# MainMatrix.net
KiCad netlist of a schematic drawn in EAGLE
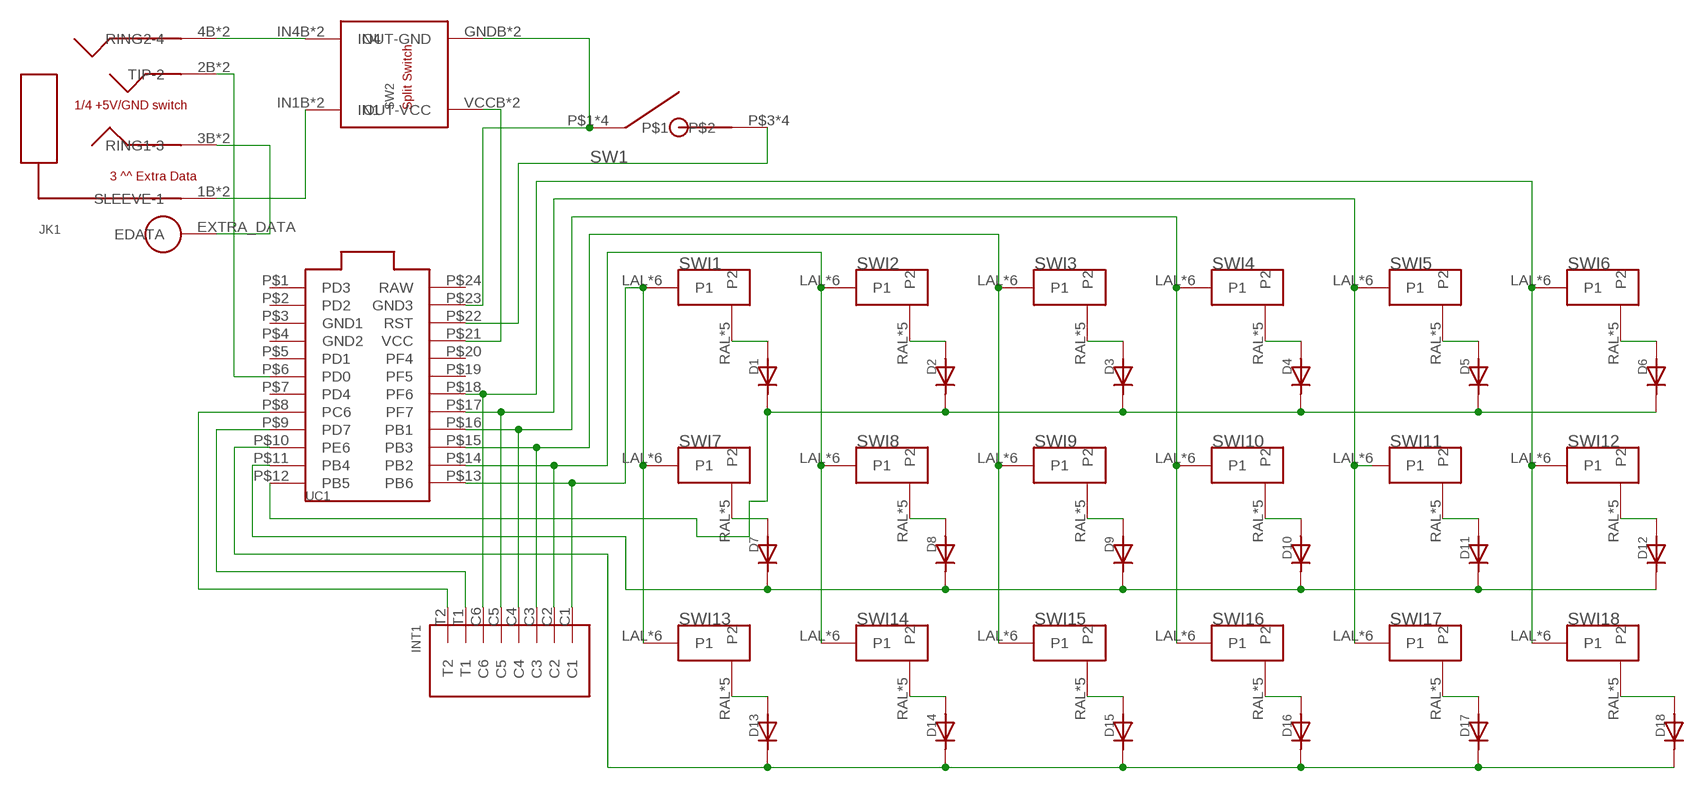
[diagram p0: schematic, sheet 1]

(export (version "E")
  (design (tool "Eeschema 10.0.6"))
  (components
    (comp (ref "D1")
      (value "DIODE")
      (footprint "eagle-import:DIODE_COMBO")
      (libsource (lib "eagle-import") (part "DIODE"))
    )
    (comp (ref "D2")
      (value "DIODE")
      (footprint "eagle-import:DIODE_COMBO")
      (libsource (lib "eagle-import") (part "DIODE"))
    )
    (comp (ref "D3")
      (value "DIODE")
      (footprint "eagle-import:DIODE_COMBO")
      (libsource (lib "eagle-import") (part "DIODE"))
    )
    (comp (ref "D4")
      (value "DIODE")
      (footprint "eagle-import:DIODE_COMBO")
      (libsource (lib "eagle-import") (part "DIODE"))
    )
    (comp (ref "D5")
      (value "DIODE")
      (footprint "eagle-import:DIODE_COMBO")
      (libsource (lib "eagle-import") (part "DIODE"))
    )
    (comp (ref "D6")
      (value "DIODE")
      (footprint "eagle-import:DIODE_COMBO")
      (libsource (lib "eagle-import") (part "DIODE"))
    )
    (comp (ref "D7")
      (value "DIODE")
      (footprint "eagle-import:DIODE_COMBO")
      (libsource (lib "eagle-import") (part "DIODE"))
    )
    (comp (ref "D8")
      (value "DIODE")
      (footprint "eagle-import:DIODE_COMBO")
      (libsource (lib "eagle-import") (part "DIODE"))
    )
    (comp (ref "D9")
      (value "DIODE")
      (footprint "eagle-import:DIODE_COMBO")
      (libsource (lib "eagle-import") (part "DIODE"))
    )
    (comp (ref "D10")
      (value "DIODE")
      (footprint "eagle-import:DIODE_COMBO")
      (libsource (lib "eagle-import") (part "DIODE"))
    )
    (comp (ref "D11")
      (value "DIODE")
      (footprint "eagle-import:DIODE_COMBO")
      (libsource (lib "eagle-import") (part "DIODE"))
    )
    (comp (ref "D12")
      (value "DIODE")
      (footprint "eagle-import:DIODE_COMBO")
      (libsource (lib "eagle-import") (part "DIODE"))
    )
    (comp (ref "D13")
      (value "DIODE")
      (footprint "eagle-import:DIODE_COMBO")
      (libsource (lib "eagle-import") (part "DIODE"))
    )
    (comp (ref "D14")
      (value "DIODE")
      (footprint "eagle-import:DIODE_COMBO")
      (libsource (lib "eagle-import") (part "DIODE"))
    )
    (comp (ref "D15")
      (value "DIODE")
      (footprint "eagle-import:DIODE_COMBO")
      (libsource (lib "eagle-import") (part "DIODE"))
    )
    (comp (ref "D16")
      (value "DIODE")
      (footprint "eagle-import:DIODE_COMBO")
      (libsource (lib "eagle-import") (part "DIODE"))
    )
    (comp (ref "D17")
      (value "DIODE")
      (footprint "eagle-import:DIODE_COMBO")
      (libsource (lib "eagle-import") (part "DIODE"))
    )
    (comp (ref "D18")
      (value "DIODE")
      (footprint "eagle-import:DIODE_COMBO")
      (libsource (lib "eagle-import") (part "DIODE"))
    )
    (comp (ref "INT1")
      (value "INTRCNNT4X2")
      (footprint "eagle-import:INTRRIBBON")
      (libsource (lib "eagle-import") (part "INTRCNNT4X2"))
    )
    (comp (ref "JK1")
      (value "TRRSJACKUNDER")
      (footprint "eagle-import:TRRSJACK")
      (libsource (lib "eagle-import") (part "TRRSJACKUNDER"))
    )
    (comp (ref "SW1")
      (value "RSTSWSMD")
      (footprint "eagle-import:FLATSWT")
      (libsource (lib "eagle-import") (part "RSTSWSMD"))
    )
    (comp (ref "SW2")
      (value "TRANSFERPADDY")
      (footprint "eagle-import:TRANSFER_PADS")
      (libsource (lib "eagle-import") (part "TRANSFERPADDY"))
    )
    (comp (ref "SWI1")
      (value "MX/ALPSDOUBLESIDED")
      (footprint "eagle-import:DOUBLED_MX_ALPS")
      (libsource (lib "eagle-import") (part "MX/ALPSDOUBLESIDED"))
    )
    (comp (ref "SWI2")
      (value "MX/ALPSDOUBLESIDED")
      (footprint "eagle-import:DOUBLED_MX_ALPS")
      (libsource (lib "eagle-import") (part "MX/ALPSDOUBLESIDED"))
    )
    (comp (ref "SWI3")
      (value "MX/ALPSDOUBLESIDED")
      (footprint "eagle-import:DOUBLED_MX_ALPS")
      (libsource (lib "eagle-import") (part "MX/ALPSDOUBLESIDED"))
    )
    (comp (ref "SWI4")
      (value "MX/ALPSDOUBLESIDED")
      (footprint "eagle-import:DOUBLED_MX_ALPS")
      (libsource (lib "eagle-import") (part "MX/ALPSDOUBLESIDED"))
    )
    (comp (ref "SWI5")
      (value "MX/ALPSDOUBLESIDED")
      (footprint "eagle-import:DOUBLED_MX_ALPS")
      (libsource (lib "eagle-import") (part "MX/ALPSDOUBLESIDED"))
    )
    (comp (ref "SWI6")
      (value "MX/ALPSDOUBLESIDED")
      (footprint "eagle-import:DOUBLED_MX_ALPS")
      (libsource (lib "eagle-import") (part "MX/ALPSDOUBLESIDED"))
    )
    (comp (ref "SWI7")
      (value "MX/ALPSDOUBLESIDED")
      (footprint "eagle-import:DOUBLED_MX_ALPS")
      (libsource (lib "eagle-import") (part "MX/ALPSDOUBLESIDED"))
    )
    (comp (ref "SWI8")
      (value "MX/ALPSDOUBLESIDED")
      (footprint "eagle-import:DOUBLED_MX_ALPS")
      (libsource (lib "eagle-import") (part "MX/ALPSDOUBLESIDED"))
    )
    (comp (ref "SWI9")
      (value "MX/ALPSDOUBLESIDED")
      (footprint "eagle-import:DOUBLED_MX_ALPS")
      (libsource (lib "eagle-import") (part "MX/ALPSDOUBLESIDED"))
    )
    (comp (ref "SWI10")
      (value "MX/ALPSDOUBLESIDED")
      (footprint "eagle-import:DOUBLED_MX_ALPS")
      (libsource (lib "eagle-import") (part "MX/ALPSDOUBLESIDED"))
    )
    (comp (ref "SWI11")
      (value "MX/ALPSDOUBLESIDED")
      (footprint "eagle-import:DOUBLED_MX_ALPS")
      (libsource (lib "eagle-import") (part "MX/ALPSDOUBLESIDED"))
    )
    (comp (ref "SWI12")
      (value "MX/ALPSDOUBLESIDED")
      (footprint "eagle-import:DOUBLED_MX_ALPS")
      (libsource (lib "eagle-import") (part "MX/ALPSDOUBLESIDED"))
    )
    (comp (ref "SWI13")
      (value "MX/ALPSDOUBLESIDED")
      (footprint "eagle-import:DOUBLED_MX_ALPS")
      (libsource (lib "eagle-import") (part "MX/ALPSDOUBLESIDED"))
    )
    (comp (ref "SWI14")
      (value "MX/ALPSDOUBLESIDED")
      (footprint "eagle-import:DOUBLED_MX_ALPS")
      (libsource (lib "eagle-import") (part "MX/ALPSDOUBLESIDED"))
    )
    (comp (ref "SWI15")
      (value "MX/ALPSDOUBLESIDED")
      (footprint "eagle-import:DOUBLED_MX_ALPS")
      (libsource (lib "eagle-import") (part "MX/ALPSDOUBLESIDED"))
    )
    (comp (ref "SWI16")
      (value "MX/ALPSDOUBLESIDED")
      (footprint "eagle-import:DOUBLED_MX_ALPS")
      (libsource (lib "eagle-import") (part "MX/ALPSDOUBLESIDED"))
    )
    (comp (ref "SWI17")
      (value "MX/ALPSDOUBLESIDED")
      (footprint "eagle-import:DOUBLED_MX_ALPS")
      (libsource (lib "eagle-import") (part "MX/ALPSDOUBLESIDED"))
    )
    (comp (ref "SWI18")
      (value "MX/ALPSDOUBLESIDED")
      (footprint "eagle-import:DOUBLED_MX_ALPS")
      (libsource (lib "eagle-import") (part "MX/ALPSDOUBLESIDED"))
    )
    (comp (ref "UC1")
      (value "PROMICROUNDER")
      (footprint "eagle-import:PROMICRO_UNDER")
      (libsource (lib "eagle-import") (part "PROMICROUNDER"))
    )
  )
  (nets
    (net (code "1") (name "Net-(D1-AN-PadANOSB)") (class "Default")
      (node (ref "D1") (pin "ANOSB") (pinfunction "AN_ANOSB") (pintype "bidirectional"))
      (node (ref "D1") (pin "ANOST") (pinfunction "AN_ANOST") (pintype "bidirectional"))
      (node (ref "D1") (pin "ANOT") (pinfunction "AN_ANOT") (pintype "bidirectional"))
      (node (ref "SWI1") (pin "RAL") (pinfunction "P2_RAL") (pintype "bidirectional"))
      (node (ref "SWI1") (pin "RAR") (pinfunction "P2_RAR") (pintype "bidirectional"))
      (node (ref "SWI1") (pin "RCL") (pinfunction "P2_RCL") (pintype "bidirectional"))
      (node (ref "SWI1") (pin "RCR") (pinfunction "P2_RCR") (pintype "bidirectional"))
      (node (ref "SWI1") (pin "RLMID") (pinfunction "P2_RLMID") (pintype "bidirectional"))
    )
    (net (code "2") (name "Net-(D2-AN-PadANOSB)") (class "Default")
      (node (ref "D2") (pin "ANOSB") (pinfunction "AN_ANOSB") (pintype "bidirectional"))
      (node (ref "D2") (pin "ANOST") (pinfunction "AN_ANOST") (pintype "bidirectional"))
      (node (ref "D2") (pin "ANOT") (pinfunction "AN_ANOT") (pintype "bidirectional"))
      (node (ref "SWI2") (pin "RAL") (pinfunction "P2_RAL") (pintype "bidirectional"))
      (node (ref "SWI2") (pin "RAR") (pinfunction "P2_RAR") (pintype "bidirectional"))
      (node (ref "SWI2") (pin "RCL") (pinfunction "P2_RCL") (pintype "bidirectional"))
      (node (ref "SWI2") (pin "RCR") (pinfunction "P2_RCR") (pintype "bidirectional"))
      (node (ref "SWI2") (pin "RLMID") (pinfunction "P2_RLMID") (pintype "bidirectional"))
    )
    (net (code "3") (name "Net-(D3-AN-PadANOSB)") (class "Default")
      (node (ref "D3") (pin "ANOSB") (pinfunction "AN_ANOSB") (pintype "bidirectional"))
      (node (ref "D3") (pin "ANOST") (pinfunction "AN_ANOST") (pintype "bidirectional"))
      (node (ref "D3") (pin "ANOT") (pinfunction "AN_ANOT") (pintype "bidirectional"))
      (node (ref "SWI3") (pin "RAL") (pinfunction "P2_RAL") (pintype "bidirectional"))
      (node (ref "SWI3") (pin "RAR") (pinfunction "P2_RAR") (pintype "bidirectional"))
      (node (ref "SWI3") (pin "RCL") (pinfunction "P2_RCL") (pintype "bidirectional"))
      (node (ref "SWI3") (pin "RCR") (pinfunction "P2_RCR") (pintype "bidirectional"))
      (node (ref "SWI3") (pin "RLMID") (pinfunction "P2_RLMID") (pintype "bidirectional"))
    )
    (net (code "4") (name "Net-(D4-AN-PadANOSB)") (class "Default")
      (node (ref "D4") (pin "ANOSB") (pinfunction "AN_ANOSB") (pintype "bidirectional"))
      (node (ref "D4") (pin "ANOST") (pinfunction "AN_ANOST") (pintype "bidirectional"))
      (node (ref "D4") (pin "ANOT") (pinfunction "AN_ANOT") (pintype "bidirectional"))
      (node (ref "SWI4") (pin "RAL") (pinfunction "P2_RAL") (pintype "bidirectional"))
      (node (ref "SWI4") (pin "RAR") (pinfunction "P2_RAR") (pintype "bidirectional"))
      (node (ref "SWI4") (pin "RCL") (pinfunction "P2_RCL") (pintype "bidirectional"))
      (node (ref "SWI4") (pin "RCR") (pinfunction "P2_RCR") (pintype "bidirectional"))
      (node (ref "SWI4") (pin "RLMID") (pinfunction "P2_RLMID") (pintype "bidirectional"))
    )
    (net (code "5") (name "Net-(D5-AN-PadANOSB)") (class "Default")
      (node (ref "D5") (pin "ANOSB") (pinfunction "AN_ANOSB") (pintype "bidirectional"))
      (node (ref "D5") (pin "ANOST") (pinfunction "AN_ANOST") (pintype "bidirectional"))
      (node (ref "D5") (pin "ANOT") (pinfunction "AN_ANOT") (pintype "bidirectional"))
      (node (ref "SWI5") (pin "RAL") (pinfunction "P2_RAL") (pintype "bidirectional"))
      (node (ref "SWI5") (pin "RAR") (pinfunction "P2_RAR") (pintype "bidirectional"))
      (node (ref "SWI5") (pin "RCL") (pinfunction "P2_RCL") (pintype "bidirectional"))
      (node (ref "SWI5") (pin "RCR") (pinfunction "P2_RCR") (pintype "bidirectional"))
      (node (ref "SWI5") (pin "RLMID") (pinfunction "P2_RLMID") (pintype "bidirectional"))
    )
    (net (code "6") (name "Net-(D6-AN-PadANOSB)") (class "Default")
      (node (ref "D6") (pin "ANOSB") (pinfunction "AN_ANOSB") (pintype "bidirectional"))
      (node (ref "D6") (pin "ANOST") (pinfunction "AN_ANOST") (pintype "bidirectional"))
      (node (ref "D6") (pin "ANOT") (pinfunction "AN_ANOT") (pintype "bidirectional"))
      (node (ref "SWI6") (pin "RAL") (pinfunction "P2_RAL") (pintype "bidirectional"))
      (node (ref "SWI6") (pin "RAR") (pinfunction "P2_RAR") (pintype "bidirectional"))
      (node (ref "SWI6") (pin "RCL") (pinfunction "P2_RCL") (pintype "bidirectional"))
      (node (ref "SWI6") (pin "RCR") (pinfunction "P2_RCR") (pintype "bidirectional"))
      (node (ref "SWI6") (pin "RLMID") (pinfunction "P2_RLMID") (pintype "bidirectional"))
    )
    (net (code "7") (name "Net-(D7-AN-PadANOSB)") (class "Default")
      (node (ref "D7") (pin "ANOSB") (pinfunction "AN_ANOSB") (pintype "bidirectional"))
      (node (ref "D7") (pin "ANOST") (pinfunction "AN_ANOST") (pintype "bidirectional"))
      (node (ref "D7") (pin "ANOT") (pinfunction "AN_ANOT") (pintype "bidirectional"))
      (node (ref "SWI7") (pin "RAL") (pinfunction "P2_RAL") (pintype "bidirectional"))
      (node (ref "SWI7") (pin "RAR") (pinfunction "P2_RAR") (pintype "bidirectional"))
      (node (ref "SWI7") (pin "RCL") (pinfunction "P2_RCL") (pintype "bidirectional"))
      (node (ref "SWI7") (pin "RCR") (pinfunction "P2_RCR") (pintype "bidirectional"))
      (node (ref "SWI7") (pin "RLMID") (pinfunction "P2_RLMID") (pintype "bidirectional"))
    )
    (net (code "8") (name "Net-(D8-AN-PadANOSB)") (class "Default")
      (node (ref "D8") (pin "ANOSB") (pinfunction "AN_ANOSB") (pintype "bidirectional"))
      (node (ref "D8") (pin "ANOST") (pinfunction "AN_ANOST") (pintype "bidirectional"))
      (node (ref "D8") (pin "ANOT") (pinfunction "AN_ANOT") (pintype "bidirectional"))
      (node (ref "SWI8") (pin "RAL") (pinfunction "P2_RAL") (pintype "bidirectional"))
      (node (ref "SWI8") (pin "RAR") (pinfunction "P2_RAR") (pintype "bidirectional"))
      (node (ref "SWI8") (pin "RCL") (pinfunction "P2_RCL") (pintype "bidirectional"))
      (node (ref "SWI8") (pin "RCR") (pinfunction "P2_RCR") (pintype "bidirectional"))
      (node (ref "SWI8") (pin "RLMID") (pinfunction "P2_RLMID") (pintype "bidirectional"))
    )
    (net (code "9") (name "Net-(D9-AN-PadANOSB)") (class "Default")
      (node (ref "D9") (pin "ANOSB") (pinfunction "AN_ANOSB") (pintype "bidirectional"))
      (node (ref "D9") (pin "ANOST") (pinfunction "AN_ANOST") (pintype "bidirectional"))
      (node (ref "D9") (pin "ANOT") (pinfunction "AN_ANOT") (pintype "bidirectional"))
      (node (ref "SWI9") (pin "RAL") (pinfunction "P2_RAL") (pintype "bidirectional"))
      (node (ref "SWI9") (pin "RAR") (pinfunction "P2_RAR") (pintype "bidirectional"))
      (node (ref "SWI9") (pin "RCL") (pinfunction "P2_RCL") (pintype "bidirectional"))
      (node (ref "SWI9") (pin "RCR") (pinfunction "P2_RCR") (pintype "bidirectional"))
      (node (ref "SWI9") (pin "RLMID") (pinfunction "P2_RLMID") (pintype "bidirectional"))
    )
    (net (code "10") (name "Net-(D10-AN-PadANOSB)") (class "Default")
      (node (ref "D10") (pin "ANOSB") (pinfunction "AN_ANOSB") (pintype "bidirectional"))
      (node (ref "D10") (pin "ANOST") (pinfunction "AN_ANOST") (pintype "bidirectional"))
      (node (ref "D10") (pin "ANOT") (pinfunction "AN_ANOT") (pintype "bidirectional"))
      (node (ref "SWI10") (pin "RAL") (pinfunction "P2_RAL") (pintype "bidirectional"))
      (node (ref "SWI10") (pin "RAR") (pinfunction "P2_RAR") (pintype "bidirectional"))
      (node (ref "SWI10") (pin "RCL") (pinfunction "P2_RCL") (pintype "bidirectional"))
      (node (ref "SWI10") (pin "RCR") (pinfunction "P2_RCR") (pintype "bidirectional"))
      (node (ref "SWI10") (pin "RLMID") (pinfunction "P2_RLMID") (pintype "bidirectional"))
    )
    (net (code "11") (name "Net-(D11-AN-PadANOSB)") (class "Default")
      (node (ref "D11") (pin "ANOSB") (pinfunction "AN_ANOSB") (pintype "bidirectional"))
      (node (ref "D11") (pin "ANOST") (pinfunction "AN_ANOST") (pintype "bidirectional"))
      (node (ref "D11") (pin "ANOT") (pinfunction "AN_ANOT") (pintype "bidirectional"))
      (node (ref "SWI11") (pin "RAL") (pinfunction "P2_RAL") (pintype "bidirectional"))
      (node (ref "SWI11") (pin "RAR") (pinfunction "P2_RAR") (pintype "bidirectional"))
      (node (ref "SWI11") (pin "RCL") (pinfunction "P2_RCL") (pintype "bidirectional"))
      (node (ref "SWI11") (pin "RCR") (pinfunction "P2_RCR") (pintype "bidirectional"))
      (node (ref "SWI11") (pin "RLMID") (pinfunction "P2_RLMID") (pintype "bidirectional"))
    )
    (net (code "12") (name "Net-(D12-AN-PadANOSB)") (class "Default")
      (node (ref "D12") (pin "ANOSB") (pinfunction "AN_ANOSB") (pintype "bidirectional"))
      (node (ref "D12") (pin "ANOST") (pinfunction "AN_ANOST") (pintype "bidirectional"))
      (node (ref "D12") (pin "ANOT") (pinfunction "AN_ANOT") (pintype "bidirectional"))
      (node (ref "SWI12") (pin "RAL") (pinfunction "P2_RAL") (pintype "bidirectional"))
      (node (ref "SWI12") (pin "RAR") (pinfunction "P2_RAR") (pintype "bidirectional"))
      (node (ref "SWI12") (pin "RCL") (pinfunction "P2_RCL") (pintype "bidirectional"))
      (node (ref "SWI12") (pin "RCR") (pinfunction "P2_RCR") (pintype "bidirectional"))
      (node (ref "SWI12") (pin "RLMID") (pinfunction "P2_RLMID") (pintype "bidirectional"))
    )
    (net (code "13") (name "Net-(D13-AN-PadANOSB)") (class "Default")
      (node (ref "D13") (pin "ANOSB") (pinfunction "AN_ANOSB") (pintype "bidirectional"))
      (node (ref "D13") (pin "ANOST") (pinfunction "AN_ANOST") (pintype "bidirectional"))
      (node (ref "D13") (pin "ANOT") (pinfunction "AN_ANOT") (pintype "bidirectional"))
      (node (ref "SWI13") (pin "RAL") (pinfunction "P2_RAL") (pintype "bidirectional"))
      (node (ref "SWI13") (pin "RAR") (pinfunction "P2_RAR") (pintype "bidirectional"))
      (node (ref "SWI13") (pin "RCL") (pinfunction "P2_RCL") (pintype "bidirectional"))
      (node (ref "SWI13") (pin "RCR") (pinfunction "P2_RCR") (pintype "bidirectional"))
      (node (ref "SWI13") (pin "RLMID") (pinfunction "P2_RLMID") (pintype "bidirectional"))
    )
    (net (code "14") (name "Net-(D14-AN-PadANOSB)") (class "Default")
      (node (ref "D14") (pin "ANOSB") (pinfunction "AN_ANOSB") (pintype "bidirectional"))
      (node (ref "D14") (pin "ANOST") (pinfunction "AN_ANOST") (pintype "bidirectional"))
      (node (ref "D14") (pin "ANOT") (pinfunction "AN_ANOT") (pintype "bidirectional"))
      (node (ref "SWI14") (pin "RAL") (pinfunction "P2_RAL") (pintype "bidirectional"))
      (node (ref "SWI14") (pin "RAR") (pinfunction "P2_RAR") (pintype "bidirectional"))
      (node (ref "SWI14") (pin "RCL") (pinfunction "P2_RCL") (pintype "bidirectional"))
      (node (ref "SWI14") (pin "RCR") (pinfunction "P2_RCR") (pintype "bidirectional"))
      (node (ref "SWI14") (pin "RLMID") (pinfunction "P2_RLMID") (pintype "bidirectional"))
    )
    (net (code "15") (name "Net-(D15-AN-PadANOSB)") (class "Default")
      (node (ref "D15") (pin "ANOSB") (pinfunction "AN_ANOSB") (pintype "bidirectional"))
      (node (ref "D15") (pin "ANOST") (pinfunction "AN_ANOST") (pintype "bidirectional"))
      (node (ref "D15") (pin "ANOT") (pinfunction "AN_ANOT") (pintype "bidirectional"))
      (node (ref "SWI15") (pin "RAL") (pinfunction "P2_RAL") (pintype "bidirectional"))
      (node (ref "SWI15") (pin "RAR") (pinfunction "P2_RAR") (pintype "bidirectional"))
      (node (ref "SWI15") (pin "RCL") (pinfunction "P2_RCL") (pintype "bidirectional"))
      (node (ref "SWI15") (pin "RCR") (pinfunction "P2_RCR") (pintype "bidirectional"))
      (node (ref "SWI15") (pin "RLMID") (pinfunction "P2_RLMID") (pintype "bidirectional"))
    )
    (net (code "16") (name "Net-(D16-AN-PadANOSB)") (class "Default")
      (node (ref "D16") (pin "ANOSB") (pinfunction "AN_ANOSB") (pintype "bidirectional"))
      (node (ref "D16") (pin "ANOST") (pinfunction "AN_ANOST") (pintype "bidirectional"))
      (node (ref "D16") (pin "ANOT") (pinfunction "AN_ANOT") (pintype "bidirectional"))
      (node (ref "SWI16") (pin "RAL") (pinfunction "P2_RAL") (pintype "bidirectional"))
      (node (ref "SWI16") (pin "RAR") (pinfunction "P2_RAR") (pintype "bidirectional"))
      (node (ref "SWI16") (pin "RCL") (pinfunction "P2_RCL") (pintype "bidirectional"))
      (node (ref "SWI16") (pin "RCR") (pinfunction "P2_RCR") (pintype "bidirectional"))
      (node (ref "SWI16") (pin "RLMID") (pinfunction "P2_RLMID") (pintype "bidirectional"))
    )
    (net (code "17") (name "Net-(D17-AN-PadANOSB)") (class "Default")
      (node (ref "D17") (pin "ANOSB") (pinfunction "AN_ANOSB") (pintype "bidirectional"))
      (node (ref "D17") (pin "ANOST") (pinfunction "AN_ANOST") (pintype "bidirectional"))
      (node (ref "D17") (pin "ANOT") (pinfunction "AN_ANOT") (pintype "bidirectional"))
      (node (ref "SWI17") (pin "RAL") (pinfunction "P2_RAL") (pintype "bidirectional"))
      (node (ref "SWI17") (pin "RAR") (pinfunction "P2_RAR") (pintype "bidirectional"))
      (node (ref "SWI17") (pin "RCL") (pinfunction "P2_RCL") (pintype "bidirectional"))
      (node (ref "SWI17") (pin "RCR") (pinfunction "P2_RCR") (pintype "bidirectional"))
      (node (ref "SWI17") (pin "RLMID") (pinfunction "P2_RLMID") (pintype "bidirectional"))
    )
    (net (code "18") (name "Net-(D18-AN-PadANOSB)") (class "Default")
      (node (ref "D18") (pin "ANOSB") (pinfunction "AN_ANOSB") (pintype "bidirectional"))
      (node (ref "D18") (pin "ANOST") (pinfunction "AN_ANOST") (pintype "bidirectional"))
      (node (ref "D18") (pin "ANOT") (pinfunction "AN_ANOT") (pintype "bidirectional"))
      (node (ref "SWI18") (pin "RAL") (pinfunction "P2_RAL") (pintype "bidirectional"))
      (node (ref "SWI18") (pin "RAR") (pinfunction "P2_RAR") (pintype "bidirectional"))
      (node (ref "SWI18") (pin "RCL") (pinfunction "P2_RCL") (pintype "bidirectional"))
      (node (ref "SWI18") (pin "RCR") (pinfunction "P2_RCR") (pintype "bidirectional"))
      (node (ref "SWI18") (pin "RLMID") (pinfunction "P2_RLMID") (pintype "bidirectional"))
    )
    (net (code "19") (name "Net-(JK1-EDATA)") (class "Default")
      (node (ref "JK1") (pin "3B") (pinfunction "RING1-3_3B") (pintype "bidirectional"))
      (node (ref "JK1") (pin "3T") (pinfunction "RING1-3_3T") (pintype "bidirectional"))
      (node (ref "JK1") (pin "EXTRA_DATA") (pinfunction "EDATA_EXTRA_DATA") (pintype "bidirectional"))
    )
    (net (code "20") (name "Net-(JK1-RING2-4-Pad4B)") (class "Default")
      (node (ref "JK1") (pin "4B") (pinfunction "RING2-4_4B") (pintype "bidirectional"))
      (node (ref "JK1") (pin "4T") (pinfunction "RING2-4_4T") (pintype "bidirectional"))
      (node (ref "SW2") (pin "IN4B") (pinfunction "IN4_IN4B") (pintype "bidirectional"))
      (node (ref "SW2") (pin "IN4T") (pinfunction "IN4_IN4T") (pintype "bidirectional"))
    )
    (net (code "21") (name "Net-(JK1-SLEEVE-1-Pad1B)") (class "Default")
      (node (ref "JK1") (pin "1B") (pinfunction "SLEEVE-1_1B") (pintype "bidirectional"))
      (node (ref "JK1") (pin "1T") (pinfunction "SLEEVE-1_1T") (pintype "bidirectional"))
      (node (ref "SW2") (pin "IN1B") (pinfunction "IN1_IN1B") (pintype "bidirectional"))
      (node (ref "SW2") (pin "IN1T") (pinfunction "IN1_IN1T") (pintype "bidirectional"))
    )
    (net (code "22") (name "Net-(UC1-GND3)") (class "Default")
      (node (ref "SW1") (pin "P$1") (pinfunction "P$1_P$1") (pintype "bidirectional"))
      (node (ref "SW1") (pin "P$2") (pinfunction "P$1_P$2") (pintype "bidirectional"))
      (node (ref "SW1") (pin "P$5") (pinfunction "P$1_P$5") (pintype "bidirectional"))
      (node (ref "SW1") (pin "P$6") (pinfunction "P$1_P$6") (pintype "bidirectional"))
      (node (ref "SW2") (pin "GNDB") (pinfunction "OUT-GND_GNDB") (pintype "bidirectional"))
      (node (ref "SW2") (pin "GNDT") (pinfunction "OUT-GND_GNDT") (pintype "bidirectional"))
      (node (ref "UC1") (pin "P$23") (pinfunction "GND3_P$23") (pintype "bidirectional"))
    )
    (net (code "23") (name "Net-(UC1-PB1)") (class "Default")
      (node (ref "INT1") (pin "C4") (pinfunction "C4_C4") (pintype "bidirectional"))
      (node (ref "SWI10") (pin "LAL") (pinfunction "P1_LAL") (pintype "bidirectional"))
      (node (ref "SWI10") (pin "LAR") (pinfunction "P1_LAR") (pintype "bidirectional"))
      (node (ref "SWI10") (pin "LCL") (pinfunction "P1_LCL") (pintype "bidirectional"))
      (node (ref "SWI10") (pin "LCR") (pinfunction "P1_LCR") (pintype "bidirectional"))
      (node (ref "SWI10") (pin "LLP") (pinfunction "P1_LLP") (pintype "bidirectional"))
      (node (ref "SWI10") (pin "LRLP") (pinfunction "P1_LRLP") (pintype "bidirectional"))
      (node (ref "SWI16") (pin "LAL") (pinfunction "P1_LAL") (pintype "bidirectional"))
      (node (ref "SWI16") (pin "LAR") (pinfunction "P1_LAR") (pintype "bidirectional"))
      (node (ref "SWI16") (pin "LCL") (pinfunction "P1_LCL") (pintype "bidirectional"))
      (node (ref "SWI16") (pin "LCR") (pinfunction "P1_LCR") (pintype "bidirectional"))
      (node (ref "SWI16") (pin "LLP") (pinfunction "P1_LLP") (pintype "bidirectional"))
      (node (ref "SWI16") (pin "LRLP") (pinfunction "P1_LRLP") (pintype "bidirectional"))
      (node (ref "SWI4") (pin "LAL") (pinfunction "P1_LAL") (pintype "bidirectional"))
      (node (ref "SWI4") (pin "LAR") (pinfunction "P1_LAR") (pintype "bidirectional"))
      (node (ref "SWI4") (pin "LCL") (pinfunction "P1_LCL") (pintype "bidirectional"))
      (node (ref "SWI4") (pin "LCR") (pinfunction "P1_LCR") (pintype "bidirectional"))
      (node (ref "SWI4") (pin "LLP") (pinfunction "P1_LLP") (pintype "bidirectional"))
      (node (ref "SWI4") (pin "LRLP") (pinfunction "P1_LRLP") (pintype "bidirectional"))
      (node (ref "UC1") (pin "P$16") (pinfunction "PB1_P$16") (pintype "bidirectional"))
    )
    (net (code "24") (name "Net-(UC1-PB2)") (class "Default")
      (node (ref "INT1") (pin "C2") (pinfunction "C2_C2") (pintype "bidirectional"))
      (node (ref "SWI14") (pin "LAL") (pinfunction "P1_LAL") (pintype "bidirectional"))
      (node (ref "SWI14") (pin "LAR") (pinfunction "P1_LAR") (pintype "bidirectional"))
      (node (ref "SWI14") (pin "LCL") (pinfunction "P1_LCL") (pintype "bidirectional"))
      (node (ref "SWI14") (pin "LCR") (pinfunction "P1_LCR") (pintype "bidirectional"))
      (node (ref "SWI14") (pin "LLP") (pinfunction "P1_LLP") (pintype "bidirectional"))
      (node (ref "SWI14") (pin "LRLP") (pinfunction "P1_LRLP") (pintype "bidirectional"))
      (node (ref "SWI2") (pin "LAL") (pinfunction "P1_LAL") (pintype "bidirectional"))
      (node (ref "SWI2") (pin "LAR") (pinfunction "P1_LAR") (pintype "bidirectional"))
      (node (ref "SWI2") (pin "LCL") (pinfunction "P1_LCL") (pintype "bidirectional"))
      (node (ref "SWI2") (pin "LCR") (pinfunction "P1_LCR") (pintype "bidirectional"))
      (node (ref "SWI2") (pin "LLP") (pinfunction "P1_LLP") (pintype "bidirectional"))
      (node (ref "SWI2") (pin "LRLP") (pinfunction "P1_LRLP") (pintype "bidirectional"))
      (node (ref "SWI8") (pin "LAL") (pinfunction "P1_LAL") (pintype "bidirectional"))
      (node (ref "SWI8") (pin "LAR") (pinfunction "P1_LAR") (pintype "bidirectional"))
      (node (ref "SWI8") (pin "LCL") (pinfunction "P1_LCL") (pintype "bidirectional"))
      (node (ref "SWI8") (pin "LCR") (pinfunction "P1_LCR") (pintype "bidirectional"))
      (node (ref "SWI8") (pin "LLP") (pinfunction "P1_LLP") (pintype "bidirectional"))
      (node (ref "SWI8") (pin "LRLP") (pinfunction "P1_LRLP") (pintype "bidirectional"))
      (node (ref "UC1") (pin "P$14") (pinfunction "PB2_P$14") (pintype "bidirectional"))
    )
    (net (code "25") (name "Net-(UC1-PB3)") (class "Default")
      (node (ref "INT1") (pin "C3") (pinfunction "C3_C3") (pintype "bidirectional"))
      (node (ref "SWI15") (pin "LAL") (pinfunction "P1_LAL") (pintype "bidirectional"))
      (node (ref "SWI15") (pin "LAR") (pinfunction "P1_LAR") (pintype "bidirectional"))
      (node (ref "SWI15") (pin "LCL") (pinfunction "P1_LCL") (pintype "bidirectional"))
      (node (ref "SWI15") (pin "LCR") (pinfunction "P1_LCR") (pintype "bidirectional"))
      (node (ref "SWI15") (pin "LLP") (pinfunction "P1_LLP") (pintype "bidirectional"))
      (node (ref "SWI15") (pin "LRLP") (pinfunction "P1_LRLP") (pintype "bidirectional"))
      (node (ref "SWI3") (pin "LAL") (pinfunction "P1_LAL") (pintype "bidirectional"))
      (node (ref "SWI3") (pin "LAR") (pinfunction "P1_LAR") (pintype "bidirectional"))
      (node (ref "SWI3") (pin "LCL") (pinfunction "P1_LCL") (pintype "bidirectional"))
      (node (ref "SWI3") (pin "LCR") (pinfunction "P1_LCR") (pintype "bidirectional"))
      (node (ref "SWI3") (pin "LLP") (pinfunction "P1_LLP") (pintype "bidirectional"))
      (node (ref "SWI3") (pin "LRLP") (pinfunction "P1_LRLP") (pintype "bidirectional"))
      (node (ref "SWI9") (pin "LAL") (pinfunction "P1_LAL") (pintype "bidirectional"))
      (node (ref "SWI9") (pin "LAR") (pinfunction "P1_LAR") (pintype "bidirectional"))
      (node (ref "SWI9") (pin "LCL") (pinfunction "P1_LCL") (pintype "bidirectional"))
      (node (ref "SWI9") (pin "LCR") (pinfunction "P1_LCR") (pintype "bidirectional"))
      (node (ref "SWI9") (pin "LLP") (pinfunction "P1_LLP") (pintype "bidirectional"))
      (node (ref "SWI9") (pin "LRLP") (pinfunction "P1_LRLP") (pintype "bidirectional"))
      (node (ref "UC1") (pin "P$15") (pinfunction "PB3_P$15") (pintype "bidirectional"))
    )
    (net (code "26") (name "Net-(UC1-PB4)") (class "Default")
      (node (ref "D10") (pin "CATSB") (pinfunction "CAT_CATSB") (pintype "bidirectional"))
      (node (ref "D10") (pin "CATST") (pinfunction "CAT_CATST") (pintype "bidirectional"))
      (node (ref "D10") (pin "CATT") (pinfunction "CAT_CATT") (pintype "bidirectional"))
      (node (ref "D11") (pin "CATSB") (pinfunction "CAT_CATSB") (pintype "bidirectional"))
      (node (ref "D11") (pin "CATST") (pinfunction "CAT_CATST") (pintype "bidirectional"))
      (node (ref "D11") (pin "CATT") (pinfunction "CAT_CATT") (pintype "bidirectional"))
      (node (ref "D12") (pin "CATSB") (pinfunction "CAT_CATSB") (pintype "bidirectional"))
      (node (ref "D12") (pin "CATST") (pinfunction "CAT_CATST") (pintype "bidirectional"))
      (node (ref "D12") (pin "CATT") (pinfunction "CAT_CATT") (pintype "bidirectional"))
      (node (ref "D7") (pin "CATSB") (pinfunction "CAT_CATSB") (pintype "bidirectional"))
      (node (ref "D7") (pin "CATST") (pinfunction "CAT_CATST") (pintype "bidirectional"))
      (node (ref "D7") (pin "CATT") (pinfunction "CAT_CATT") (pintype "bidirectional"))
      (node (ref "D8") (pin "CATSB") (pinfunction "CAT_CATSB") (pintype "bidirectional"))
      (node (ref "D8") (pin "CATST") (pinfunction "CAT_CATST") (pintype "bidirectional"))
      (node (ref "D8") (pin "CATT") (pinfunction "CAT_CATT") (pintype "bidirectional"))
      (node (ref "D9") (pin "CATSB") (pinfunction "CAT_CATSB") (pintype "bidirectional"))
      (node (ref "D9") (pin "CATST") (pinfunction "CAT_CATST") (pintype "bidirectional"))
      (node (ref "D9") (pin "CATT") (pinfunction "CAT_CATT") (pintype "bidirectional"))
      (node (ref "UC1") (pin "P$11") (pinfunction "PB4_P$11") (pintype "bidirectional"))
    )
    (net (code "27") (name "Net-(UC1-PB5)") (class "Default")
      (node (ref "D1") (pin "CATSB") (pinfunction "CAT_CATSB") (pintype "bidirectional"))
      (node (ref "D1") (pin "CATST") (pinfunction "CAT_CATST") (pintype "bidirectional"))
      (node (ref "D1") (pin "CATT") (pinfunction "CAT_CATT") (pintype "bidirectional"))
      (node (ref "D2") (pin "CATSB") (pinfunction "CAT_CATSB") (pintype "bidirectional"))
      (node (ref "D2") (pin "CATST") (pinfunction "CAT_CATST") (pintype "bidirectional"))
      (node (ref "D2") (pin "CATT") (pinfunction "CAT_CATT") (pintype "bidirectional"))
      (node (ref "D3") (pin "CATSB") (pinfunction "CAT_CATSB") (pintype "bidirectional"))
      (node (ref "D3") (pin "CATST") (pinfunction "CAT_CATST") (pintype "bidirectional"))
      (node (ref "D3") (pin "CATT") (pinfunction "CAT_CATT") (pintype "bidirectional"))
      (node (ref "D4") (pin "CATSB") (pinfunction "CAT_CATSB") (pintype "bidirectional"))
      (node (ref "D4") (pin "CATST") (pinfunction "CAT_CATST") (pintype "bidirectional"))
      (node (ref "D4") (pin "CATT") (pinfunction "CAT_CATT") (pintype "bidirectional"))
      (node (ref "D5") (pin "CATSB") (pinfunction "CAT_CATSB") (pintype "bidirectional"))
      (node (ref "D5") (pin "CATST") (pinfunction "CAT_CATST") (pintype "bidirectional"))
      (node (ref "D5") (pin "CATT") (pinfunction "CAT_CATT") (pintype "bidirectional"))
      (node (ref "D6") (pin "CATSB") (pinfunction "CAT_CATSB") (pintype "bidirectional"))
      (node (ref "D6") (pin "CATST") (pinfunction "CAT_CATST") (pintype "bidirectional"))
      (node (ref "D6") (pin "CATT") (pinfunction "CAT_CATT") (pintype "bidirectional"))
      (node (ref "UC1") (pin "P$12") (pinfunction "PB5_P$12") (pintype "bidirectional"))
    )
    (net (code "28") (name "Net-(UC1-PB6)") (class "Default")
      (node (ref "INT1") (pin "C1") (pinfunction "C1_C1") (pintype "bidirectional"))
      (node (ref "SWI1") (pin "LAL") (pinfunction "P1_LAL") (pintype "bidirectional"))
      (node (ref "SWI1") (pin "LAR") (pinfunction "P1_LAR") (pintype "bidirectional"))
      (node (ref "SWI1") (pin "LCL") (pinfunction "P1_LCL") (pintype "bidirectional"))
      (node (ref "SWI1") (pin "LCR") (pinfunction "P1_LCR") (pintype "bidirectional"))
      (node (ref "SWI1") (pin "LLP") (pinfunction "P1_LLP") (pintype "bidirectional"))
      (node (ref "SWI1") (pin "LRLP") (pinfunction "P1_LRLP") (pintype "bidirectional"))
      (node (ref "SWI13") (pin "LAL") (pinfunction "P1_LAL") (pintype "bidirectional"))
      (node (ref "SWI13") (pin "LAR") (pinfunction "P1_LAR") (pintype "bidirectional"))
      (node (ref "SWI13") (pin "LCL") (pinfunction "P1_LCL") (pintype "bidirectional"))
      (node (ref "SWI13") (pin "LCR") (pinfunction "P1_LCR") (pintype "bidirectional"))
      (node (ref "SWI13") (pin "LLP") (pinfunction "P1_LLP") (pintype "bidirectional"))
      (node (ref "SWI13") (pin "LRLP") (pinfunction "P1_LRLP") (pintype "bidirectional"))
      (node (ref "SWI7") (pin "LAL") (pinfunction "P1_LAL") (pintype "bidirectional"))
      (node (ref "SWI7") (pin "LAR") (pinfunction "P1_LAR") (pintype "bidirectional"))
      (node (ref "SWI7") (pin "LCL") (pinfunction "P1_LCL") (pintype "bidirectional"))
      (node (ref "SWI7") (pin "LCR") (pinfunction "P1_LCR") (pintype "bidirectional"))
      (node (ref "SWI7") (pin "LLP") (pinfunction "P1_LLP") (pintype "bidirectional"))
      (node (ref "SWI7") (pin "LRLP") (pinfunction "P1_LRLP") (pintype "bidirectional"))
      (node (ref "UC1") (pin "P$13") (pinfunction "PB6_P$13") (pintype "bidirectional"))
    )
    (net (code "29") (name "Net-(UC1-PC6)") (class "Default")
      (node (ref "INT1") (pin "T2") (pinfunction "T2_T2") (pintype "bidirectional"))
      (node (ref "UC1") (pin "P$8") (pinfunction "PC6_P$8") (pintype "bidirectional"))
    )
    (net (code "30") (name "Net-(UC1-PD0)") (class "Default")
      (node (ref "JK1") (pin "2B") (pinfunction "TIP-2_2B") (pintype "bidirectional"))
      (node (ref "JK1") (pin "2T") (pinfunction "TIP-2_2T") (pintype "bidirectional"))
      (node (ref "UC1") (pin "P$6") (pinfunction "PD0_P$6") (pintype "bidirectional"))
    )
    (net (code "31") (name "Net-(UC1-PD7)") (class "Default")
      (node (ref "INT1") (pin "T1") (pinfunction "T1_T1") (pintype "bidirectional"))
      (node (ref "UC1") (pin "P$9") (pinfunction "PD7_P$9") (pintype "bidirectional"))
    )
    (net (code "32") (name "Net-(UC1-PE6)") (class "Default")
      (node (ref "D13") (pin "CATSB") (pinfunction "CAT_CATSB") (pintype "bidirectional"))
      (node (ref "D13") (pin "CATST") (pinfunction "CAT_CATST") (pintype "bidirectional"))
      (node (ref "D13") (pin "CATT") (pinfunction "CAT_CATT") (pintype "bidirectional"))
      (node (ref "D14") (pin "CATSB") (pinfunction "CAT_CATSB") (pintype "bidirectional"))
      (node (ref "D14") (pin "CATST") (pinfunction "CAT_CATST") (pintype "bidirectional"))
      (node (ref "D14") (pin "CATT") (pinfunction "CAT_CATT") (pintype "bidirectional"))
      (node (ref "D15") (pin "CATSB") (pinfunction "CAT_CATSB") (pintype "bidirectional"))
      (node (ref "D15") (pin "CATST") (pinfunction "CAT_CATST") (pintype "bidirectional"))
      (node (ref "D15") (pin "CATT") (pinfunction "CAT_CATT") (pintype "bidirectional"))
      (node (ref "D16") (pin "CATSB") (pinfunction "CAT_CATSB") (pintype "bidirectional"))
      (node (ref "D16") (pin "CATST") (pinfunction "CAT_CATST") (pintype "bidirectional"))
      (node (ref "D16") (pin "CATT") (pinfunction "CAT_CATT") (pintype "bidirectional"))
      (node (ref "D17") (pin "CATSB") (pinfunction "CAT_CATSB") (pintype "bidirectional"))
      (node (ref "D17") (pin "CATST") (pinfunction "CAT_CATST") (pintype "bidirectional"))
      (node (ref "D17") (pin "CATT") (pinfunction "CAT_CATT") (pintype "bidirectional"))
      (node (ref "D18") (pin "CATSB") (pinfunction "CAT_CATSB") (pintype "bidirectional"))
      (node (ref "D18") (pin "CATST") (pinfunction "CAT_CATST") (pintype "bidirectional"))
      (node (ref "D18") (pin "CATT") (pinfunction "CAT_CATT") (pintype "bidirectional"))
      (node (ref "UC1") (pin "P$10") (pinfunction "PE6_P$10") (pintype "bidirectional"))
    )
    (net (code "33") (name "Net-(UC1-PF6)") (class "Default")
      (node (ref "INT1") (pin "C6") (pinfunction "C6_C6") (pintype "bidirectional"))
      (node (ref "SWI12") (pin "LAL") (pinfunction "P1_LAL") (pintype "bidirectional"))
      (node (ref "SWI12") (pin "LAR") (pinfunction "P1_LAR") (pintype "bidirectional"))
      (node (ref "SWI12") (pin "LCL") (pinfunction "P1_LCL") (pintype "bidirectional"))
      (node (ref "SWI12") (pin "LCR") (pinfunction "P1_LCR") (pintype "bidirectional"))
      (node (ref "SWI12") (pin "LLP") (pinfunction "P1_LLP") (pintype "bidirectional"))
      (node (ref "SWI12") (pin "LRLP") (pinfunction "P1_LRLP") (pintype "bidirectional"))
      (node (ref "SWI18") (pin "LAL") (pinfunction "P1_LAL") (pintype "bidirectional"))
      (node (ref "SWI18") (pin "LAR") (pinfunction "P1_LAR") (pintype "bidirectional"))
      (node (ref "SWI18") (pin "LCL") (pinfunction "P1_LCL") (pintype "bidirectional"))
      (node (ref "SWI18") (pin "LCR") (pinfunction "P1_LCR") (pintype "bidirectional"))
      (node (ref "SWI18") (pin "LLP") (pinfunction "P1_LLP") (pintype "bidirectional"))
      (node (ref "SWI18") (pin "LRLP") (pinfunction "P1_LRLP") (pintype "bidirectional"))
      (node (ref "SWI6") (pin "LAL") (pinfunction "P1_LAL") (pintype "bidirectional"))
      (node (ref "SWI6") (pin "LAR") (pinfunction "P1_LAR") (pintype "bidirectional"))
      (node (ref "SWI6") (pin "LCL") (pinfunction "P1_LCL") (pintype "bidirectional"))
      (node (ref "SWI6") (pin "LCR") (pinfunction "P1_LCR") (pintype "bidirectional"))
      (node (ref "SWI6") (pin "LLP") (pinfunction "P1_LLP") (pintype "bidirectional"))
      (node (ref "SWI6") (pin "LRLP") (pinfunction "P1_LRLP") (pintype "bidirectional"))
      (node (ref "UC1") (pin "P$18") (pinfunction "PF6_P$18") (pintype "bidirectional"))
    )
    (net (code "34") (name "Net-(UC1-PF7)") (class "Default")
      (node (ref "INT1") (pin "C5") (pinfunction "C5_C5") (pintype "bidirectional"))
      (node (ref "SWI11") (pin "LAL") (pinfunction "P1_LAL") (pintype "bidirectional"))
      (node (ref "SWI11") (pin "LAR") (pinfunction "P1_LAR") (pintype "bidirectional"))
      (node (ref "SWI11") (pin "LCL") (pinfunction "P1_LCL") (pintype "bidirectional"))
      (node (ref "SWI11") (pin "LCR") (pinfunction "P1_LCR") (pintype "bidirectional"))
      (node (ref "SWI11") (pin "LLP") (pinfunction "P1_LLP") (pintype "bidirectional"))
      (node (ref "SWI11") (pin "LRLP") (pinfunction "P1_LRLP") (pintype "bidirectional"))
      (node (ref "SWI17") (pin "LAL") (pinfunction "P1_LAL") (pintype "bidirectional"))
      (node (ref "SWI17") (pin "LAR") (pinfunction "P1_LAR") (pintype "bidirectional"))
      (node (ref "SWI17") (pin "LCL") (pinfunction "P1_LCL") (pintype "bidirectional"))
      (node (ref "SWI17") (pin "LCR") (pinfunction "P1_LCR") (pintype "bidirectional"))
      (node (ref "SWI17") (pin "LLP") (pinfunction "P1_LLP") (pintype "bidirectional"))
      (node (ref "SWI17") (pin "LRLP") (pinfunction "P1_LRLP") (pintype "bidirectional"))
      (node (ref "SWI5") (pin "LAL") (pinfunction "P1_LAL") (pintype "bidirectional"))
      (node (ref "SWI5") (pin "LAR") (pinfunction "P1_LAR") (pintype "bidirectional"))
      (node (ref "SWI5") (pin "LCL") (pinfunction "P1_LCL") (pintype "bidirectional"))
      (node (ref "SWI5") (pin "LCR") (pinfunction "P1_LCR") (pintype "bidirectional"))
      (node (ref "SWI5") (pin "LLP") (pinfunction "P1_LLP") (pintype "bidirectional"))
      (node (ref "SWI5") (pin "LRLP") (pinfunction "P1_LRLP") (pintype "bidirectional"))
      (node (ref "UC1") (pin "P$17") (pinfunction "PF7_P$17") (pintype "bidirectional"))
    )
    (net (code "35") (name "Net-(UC1-RST)") (class "Default")
      (node (ref "SW1") (pin "P$3") (pinfunction "P$2_P$3") (pintype "bidirectional"))
      (node (ref "SW1") (pin "P$4") (pinfunction "P$2_P$4") (pintype "bidirectional"))
      (node (ref "SW1") (pin "P$7") (pinfunction "P$2_P$7") (pintype "bidirectional"))
      (node (ref "SW1") (pin "P$8") (pinfunction "P$2_P$8") (pintype "bidirectional"))
      (node (ref "UC1") (pin "P$22") (pinfunction "RST_P$22") (pintype "bidirectional"))
    )
    (net (code "36") (name "Net-(UC1-VCC)") (class "Default")
      (node (ref "SW2") (pin "VCCB") (pinfunction "OUT-VCC_VCCB") (pintype "bidirectional"))
      (node (ref "SW2") (pin "VCCT") (pinfunction "OUT-VCC_VCCT") (pintype "bidirectional"))
      (node (ref "UC1") (pin "P$21") (pinfunction "VCC_P$21") (pintype "bidirectional"))
    )
    (net (code "37") (name "unconnected-(UC1-GND1-PadP$3)") (class "Default")
      (node (ref "UC1") (pin "P$3") (pinfunction "GND1_P$3") (pintype "bidirectional"))
    )
    (net (code "38") (name "unconnected-(UC1-GND2-PadP$4)") (class "Default")
      (node (ref "UC1") (pin "P$4") (pinfunction "GND2_P$4") (pintype "bidirectional"))
    )
    (net (code "39") (name "unconnected-(UC1-PD1-PadP$5)") (class "Default")
      (node (ref "UC1") (pin "P$5") (pinfunction "PD1_P$5") (pintype "bidirectional"))
    )
    (net (code "40") (name "unconnected-(UC1-PD2-PadP$2)") (class "Default")
      (node (ref "UC1") (pin "P$2") (pinfunction "PD2_P$2") (pintype "bidirectional"))
    )
    (net (code "41") (name "unconnected-(UC1-PD3-PadP$1)") (class "Default")
      (node (ref "UC1") (pin "P$1") (pinfunction "PD3_P$1") (pintype "bidirectional"))
    )
    (net (code "42") (name "unconnected-(UC1-PD4-PadP$7)") (class "Default")
      (node (ref "UC1") (pin "P$7") (pinfunction "PD4_P$7") (pintype "bidirectional"))
    )
    (net (code "43") (name "unconnected-(UC1-PF4-PadP$20)") (class "Default")
      (node (ref "UC1") (pin "P$20") (pinfunction "PF4_P$20") (pintype "bidirectional"))
    )
    (net (code "44") (name "unconnected-(UC1-PF5-PadP$19)") (class "Default")
      (node (ref "UC1") (pin "P$19") (pinfunction "PF5_P$19") (pintype "bidirectional"))
    )
    (net (code "45") (name "unconnected-(UC1-RAW-PadP$24)") (class "Default")
      (node (ref "UC1") (pin "P$24") (pinfunction "RAW_P$24") (pintype "bidirectional"))
    )
  )
)
